# 03_MCU1.net
KiCad netlist of a schematic drawn in Altium Designer
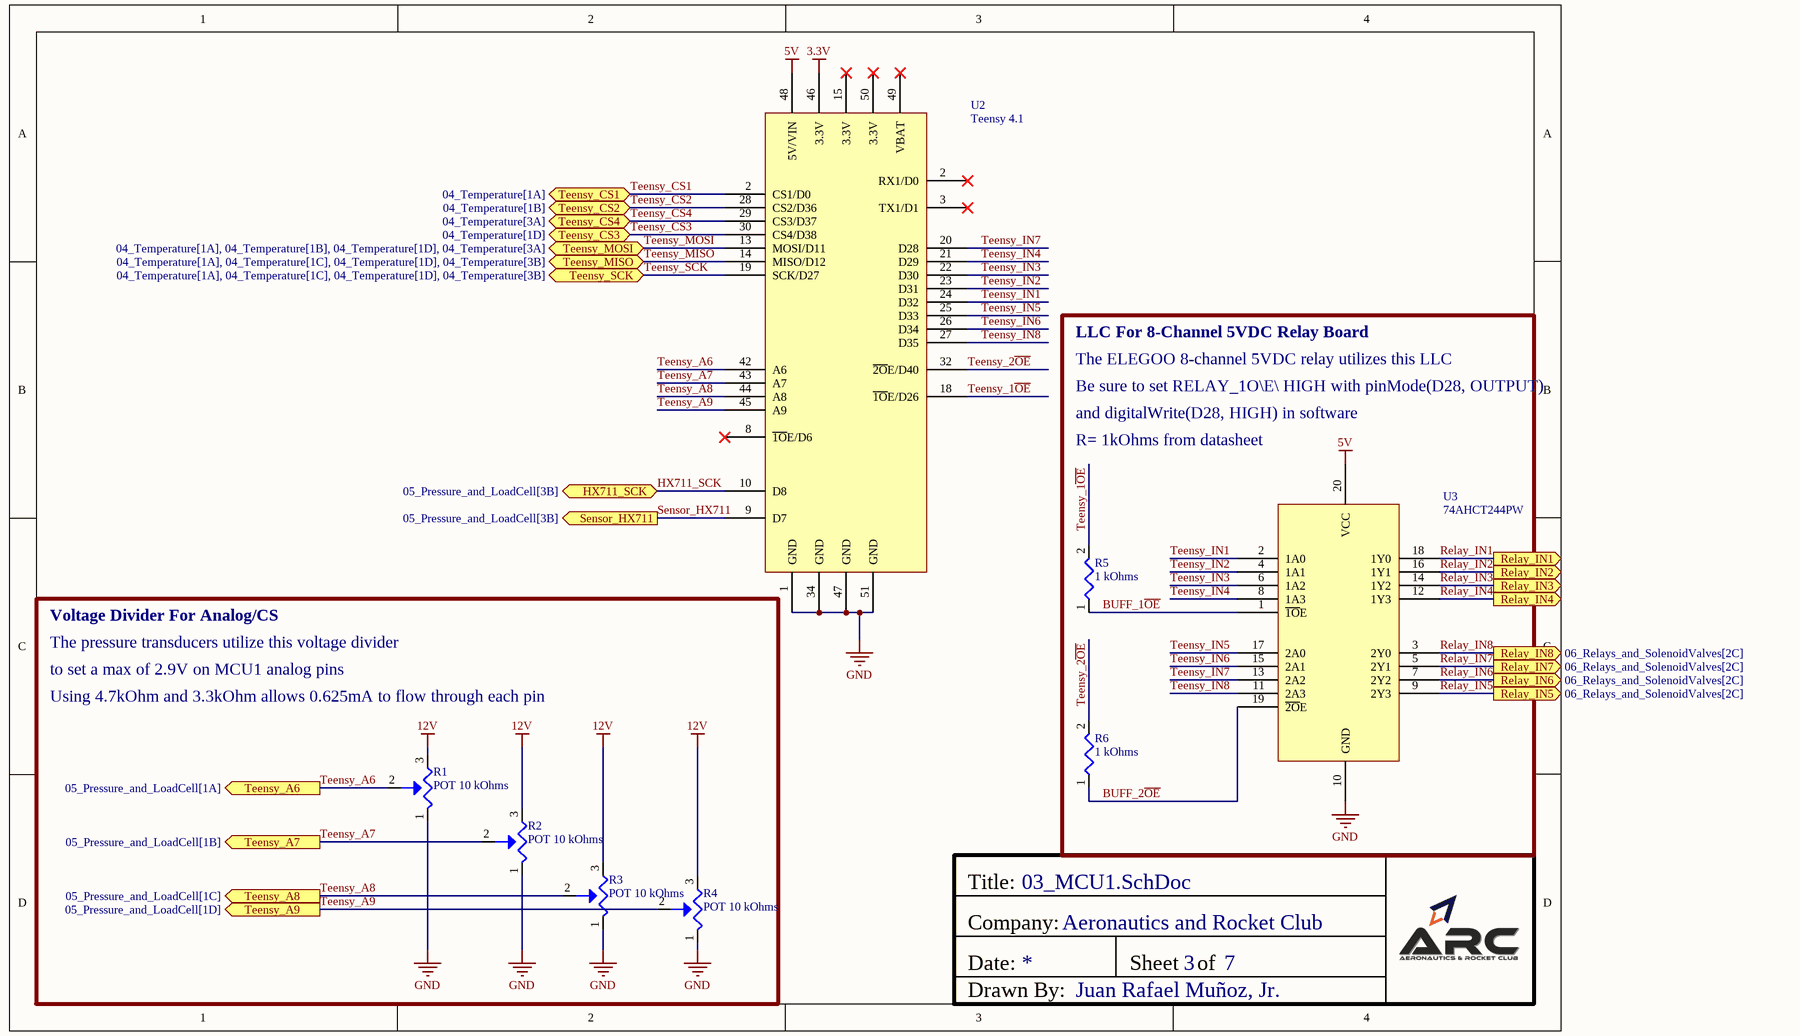
[diagram p0: 03_MCU1.SchDoc]

(export (version "E")
  (design (tool "Eeschema 10.0.6"))
  (components
    (comp (ref "R1")
      (value "POT 10 kOhms")
      (footprint "3296WL 10K POT")
      (description "10 kOhms 0.5W, 1/2W PC Pins Through Hole Trimmer Potentiometer Cermet 25.0 Turn Top Adjustment")
      (fields
        (field (name "MANUFACTURER") "Bourns")
        (field (name "MANUFACTURER PART NUMBER") "3296W-1-103LF")
      )
      (libsource (lib "Ground Support_Schlib") (part "3296W-1-103LF"))
    )
    (comp (ref "R2")
      (value "POT 10 kOhms")
      (footprint "3296WL 10K POT")
      (description "10 kOhms 0.5W, 1/2W PC Pins Through Hole Trimmer Potentiometer Cermet 25.0 Turn Top Adjustment")
      (fields
        (field (name "MANUFACTURER") "Bourns")
        (field (name "MANUFACTURER PART NUMBER") "3296W-1-103LF")
      )
      (libsource (lib "Ground Support_Schlib") (part "3296W-1-103LF"))
    )
    (comp (ref "R3")
      (value "POT 10 kOhms")
      (footprint "3296WL 10K POT")
      (description "10 kOhms 0.5W, 1/2W PC Pins Through Hole Trimmer Potentiometer Cermet 25.0 Turn Top Adjustment")
      (fields
        (field (name "MANUFACTURER") "Bourns")
        (field (name "MANUFACTURER PART NUMBER") "3296W-1-103LF")
      )
      (libsource (lib "Ground Support_Schlib") (part "3296W-1-103LF"))
    )
    (comp (ref "R4")
      (value "POT 10 kOhms")
      (footprint "3296WL 10K POT")
      (description "10 kOhms 0.5W, 1/2W PC Pins Through Hole Trimmer Potentiometer Cermet 25.0 Turn Top Adjustment")
      (fields
        (field (name "MANUFACTURER") "Bourns")
        (field (name "MANUFACTURER PART NUMBER") "3296W-1-103LF")
      )
      (libsource (lib "Ground Support_Schlib") (part "3296W-1-103LF"))
    )
    (comp (ref "R5")
      (value "1 kOhms")
      (footprint "RESC2012X06N")
      (description "1 kOhms ±1% 0.25W, 1/4W Chip Resistor 0805 (2012 Metric) Moisture Resistant Thick Film")
      (fields
        (field (name "MANUFACTURER") "Yageo")
        (field (name "MANUFACTURER PART NUMBER") "RC0805FR-7W1KL")
      )
      (libsource (lib "Ground Support_Schlib") (part "RC0805FR-7W1KL Yageo"))
    )
    (comp (ref "R6")
      (value "1 kOhms")
      (footprint "RESC2012X06N")
      (description "1 kOhms ±1% 0.25W, 1/4W Chip Resistor 0805 (2012 Metric) Moisture Resistant Thick Film")
      (fields
        (field (name "MANUFACTURER") "Yageo")
        (field (name "MANUFACTURER PART NUMBER") "RC0805FR-7W1KL")
      )
      (libsource (lib "Ground Support_Schlib") (part "RC0805FR-7W1KL Yageo"))
    )
    (comp (ref "U2")
      (value "Teensy 4.1")
      (footprint "Teensy 4.1")
      (fields (field (name "MANUFACTURER") "SparkFun") (field (name "MANUFACTURER PART NUMBER") "DEV-16996"))
      (libsource (lib "Ground Support_Schlib") (part "Teensy 4.1"))
    )
    (comp (ref "U3")
      (value "74AHCT244PW")
      (footprint "74AHCT244PW")
      (description "Octal Tri-State Buffer NON-INVERT 5.5V 20TSSOP")
      (fields
        (field (name "MANUFACTURER") "NXP Semiconductors")
        (field (name "MANUFACTURER PART NUMBER") "74AHCT244PW,118")
      )
      (libsource (lib "Ground Support_Schlib") (part "74AHCT244PW"))
    )
  )
  (nets
    (net (code "1") (name "/BUFF_1~{OE}") (class "Default")
      (node (ref "R5") (pin "1") (pinfunction "1_1") (pintype "passive"))
      (node (ref "U3") (pin "1") (pinfunction "~{1O}E_1") (pintype "passive"))
    )
    (net (code "2") (name "/BUFF_2~{OE}") (class "Default")
      (node (ref "R6") (pin "1") (pinfunction "1_1") (pintype "passive"))
      (node (ref "U3") (pin "19") (pinfunction "~{2O}E_19") (pintype "passive"))
    )
    (net (code "3") (name "/HX711_SCK") (class "Default")
      (node (ref "U2") (pin "10") (pinfunction "D8_10") (pintype "passive"))
    )
    (net (code "4") (name "/Relay_IN1") (class "Default")
      (node (ref "U3") (pin "18") (pinfunction "1Y0_18") (pintype "passive"))
    )
    (net (code "5") (name "/Relay_IN2") (class "Default")
      (node (ref "U3") (pin "16") (pinfunction "1Y1_16") (pintype "passive"))
    )
    (net (code "6") (name "/Relay_IN3") (class "Default")
      (node (ref "U3") (pin "14") (pinfunction "1Y2_14") (pintype "passive"))
    )
    (net (code "7") (name "/Relay_IN4") (class "Default")
      (node (ref "U3") (pin "12") (pinfunction "1Y3_12") (pintype "passive"))
    )
    (net (code "8") (name "/Relay_IN5") (class "Default")
      (node (ref "U3") (pin "9") (pinfunction "2Y3_9") (pintype "passive"))
    )
    (net (code "9") (name "/Relay_IN6") (class "Default")
      (node (ref "U3") (pin "7") (pinfunction "2Y2_7") (pintype "passive"))
    )
    (net (code "10") (name "/Relay_IN7") (class "Default")
      (node (ref "U3") (pin "5") (pinfunction "2Y1_5") (pintype "passive"))
    )
    (net (code "11") (name "/Relay_IN8") (class "Default")
      (node (ref "U3") (pin "3") (pinfunction "2Y0_3") (pintype "passive"))
    )
    (net (code "12") (name "/Sensor_HX711") (class "Default")
      (node (ref "U2") (pin "9") (pinfunction "D7_9") (pintype "passive"))
    )
    (net (code "13") (name "/Teensy_1~{OE}") (class "Default")
      (node (ref "R5") (pin "2") (pinfunction "2_2") (pintype "passive"))
      (node (ref "U2") (pin "18") (pinfunction "~{1O}E/D26_18") (pintype "passive"))
    )
    (net (code "14") (name "/Teensy_2~{OE}") (class "Default")
      (node (ref "R6") (pin "2") (pinfunction "2_2") (pintype "passive"))
      (node (ref "U2") (pin "32") (pinfunction "~{2O}E/D40_32") (pintype "passive"))
    )
    (net (code "15") (name "/Teensy_A6") (class "Default")
      (node (ref "R1") (pin "2") (pinfunction "2_2") (pintype "passive"))
      (node (ref "U2") (pin "42") (pinfunction "A6_42") (pintype "passive"))
    )
    (net (code "16") (name "/Teensy_A7") (class "Default")
      (node (ref "R2") (pin "2") (pinfunction "2_2") (pintype "passive"))
      (node (ref "U2") (pin "43") (pinfunction "A7_43") (pintype "passive"))
    )
    (net (code "17") (name "/Teensy_A8") (class "Default")
      (node (ref "R3") (pin "2") (pinfunction "2_2") (pintype "passive"))
      (node (ref "U2") (pin "44") (pinfunction "A8_44") (pintype "passive"))
    )
    (net (code "18") (name "/Teensy_A9") (class "Default")
      (node (ref "R4") (pin "2") (pinfunction "2_2") (pintype "passive"))
      (node (ref "U2") (pin "45") (pinfunction "A9_45") (pintype "passive"))
    )
    (net (code "19") (name "/Teensy_CS1") (class "Default")
      (node (ref "U2") (pin "2") (pinfunction "CS1/D0_2") (pintype "passive"))
    )
    (net (code "20") (name "/Teensy_CS2") (class "Default")
      (node (ref "U2") (pin "28") (pinfunction "CS2/D36_28") (pintype "passive"))
    )
    (net (code "21") (name "/Teensy_CS3") (class "Default")
      (node (ref "U2") (pin "30") (pinfunction "CS4/D38_30") (pintype "passive"))
    )
    (net (code "22") (name "/Teensy_CS4") (class "Default")
      (node (ref "U2") (pin "29") (pinfunction "CS3/D37_29") (pintype "passive"))
    )
    (net (code "23") (name "/Teensy_IN1") (class "Default")
      (node (ref "U2") (pin "24") (pinfunction "D32_24") (pintype "passive"))
      (node (ref "U3") (pin "2") (pinfunction "1A0_2") (pintype "passive"))
    )
    (net (code "24") (name "/Teensy_IN2") (class "Default")
      (node (ref "U2") (pin "23") (pinfunction "D31_23") (pintype "passive"))
      (node (ref "U3") (pin "4") (pinfunction "1A1_4") (pintype "passive"))
    )
    (net (code "25") (name "/Teensy_IN3") (class "Default")
      (node (ref "U2") (pin "22") (pinfunction "D30_22") (pintype "passive"))
      (node (ref "U3") (pin "6") (pinfunction "1A2_6") (pintype "passive"))
    )
    (net (code "26") (name "/Teensy_IN4") (class "Default")
      (node (ref "U2") (pin "21") (pinfunction "D29_21") (pintype "passive"))
      (node (ref "U3") (pin "8") (pinfunction "1A3_8") (pintype "passive"))
    )
    (net (code "27") (name "/Teensy_IN5") (class "Default")
      (node (ref "U2") (pin "25") (pinfunction "D33_25") (pintype "passive"))
      (node (ref "U3") (pin "17") (pinfunction "2A0_17") (pintype "passive"))
    )
    (net (code "28") (name "/Teensy_IN6") (class "Default")
      (node (ref "U2") (pin "26") (pinfunction "D34_26") (pintype "passive"))
      (node (ref "U3") (pin "15") (pinfunction "2A1_15") (pintype "passive"))
    )
    (net (code "29") (name "/Teensy_IN7") (class "Default")
      (node (ref "U2") (pin "20") (pinfunction "D28_20") (pintype "passive"))
      (node (ref "U3") (pin "13") (pinfunction "2A2_13") (pintype "passive"))
    )
    (net (code "30") (name "/Teensy_IN8") (class "Default")
      (node (ref "U2") (pin "27") (pinfunction "D35_27") (pintype "passive"))
      (node (ref "U3") (pin "11") (pinfunction "2A3_11") (pintype "passive"))
    )
    (net (code "31") (name "/Teensy_MISO") (class "Default")
      (node (ref "U2") (pin "14") (pinfunction "MISO/D12_14") (pintype "passive"))
    )
    (net (code "32") (name "/Teensy_MOSI") (class "Default")
      (node (ref "U2") (pin "13") (pinfunction "MOSI/D11_13") (pintype "passive"))
    )
    (net (code "33") (name "/Teensy_SCK") (class "Default")
      (node (ref "U2") (pin "19") (pinfunction "SCK/D27_19") (pintype "passive"))
    )
    (net (code "34") (name "3.3V") (class "Default")
      (node (ref "U2") (pin "46") (pinfunction "3.3V_46") (pintype "passive"))
    )
    (net (code "35") (name "5V") (class "Default")
      (node (ref "U2") (pin "48") (pinfunction "5V/VIN_48") (pintype "passive"))
      (node (ref "U3") (pin "20") (pinfunction "VCC_20") (pintype "passive"))
    )
    (net (code "36") (name "12V") (class "Default")
      (node (ref "R1") (pin "3") (pinfunction "3_3") (pintype "passive"))
      (node (ref "R2") (pin "3") (pinfunction "3_3") (pintype "passive"))
      (node (ref "R3") (pin "3") (pinfunction "3_3") (pintype "passive"))
      (node (ref "R4") (pin "3") (pinfunction "3_3") (pintype "passive"))
    )
    (net (code "37") (name "GND") (class "Default")
      (node (ref "R1") (pin "1") (pinfunction "1_1") (pintype "passive"))
      (node (ref "R2") (pin "1") (pinfunction "1_1") (pintype "passive"))
      (node (ref "R3") (pin "1") (pinfunction "1_1") (pintype "passive"))
      (node (ref "R4") (pin "1") (pinfunction "1_1") (pintype "passive"))
      (node (ref "U2") (pin "1") (pinfunction "GND_1") (pintype "passive"))
      (node (ref "U2") (pin "34") (pinfunction "GND_34") (pintype "passive"))
      (node (ref "U2") (pin "47") (pinfunction "GND_47") (pintype "passive"))
      (node (ref "U2") (pin "51") (pinfunction "GND_51") (pintype "passive"))
      (node (ref "U3") (pin "10") (pinfunction "GND_10") (pintype "passive"))
    )
    (net (code "38") (name "unconnected-(U2-3.3V-Pad15)") (class "Default")
      (node (ref "U2") (pin "15") (pinfunction "3.3V_15") (pintype "passive+no_connect"))
    )
    (net (code "39") (name "unconnected-(U2-3.3V-Pad50)") (class "Default")
      (node (ref "U2") (pin "50") (pinfunction "3.3V_50") (pintype "passive+no_connect"))
    )
    (net (code "40") (name "unconnected-(U2-RX1{slash}D0-Pad2)") (class "Default")
      (node (ref "U2") (pin "2") (pinfunction "RX1/D0_2") (pintype "passive+no_connect"))
    )
    (net (code "41") (name "unconnected-(U2-TX1{slash}D1-Pad3)") (class "Default")
      (node (ref "U2") (pin "3") (pinfunction "TX1/D1_3") (pintype "passive+no_connect"))
    )
    (net (code "42") (name "unconnected-(U2-VBAT-Pad49)") (class "Default")
      (node (ref "U2") (pin "49") (pinfunction "VBAT_49") (pintype "passive+no_connect"))
    )
    (net (code "43") (name "unconnected-(U2-~{1O}E{slash}D6-Pad8)") (class "Default")
      (node (ref "U2") (pin "8") (pinfunction "~{1O}E/D6_8") (pintype "passive+no_connect"))
    )
  )
)
